# Arriquitaun2.net
KiCad netlist of a schematic drawn in Altium Designer
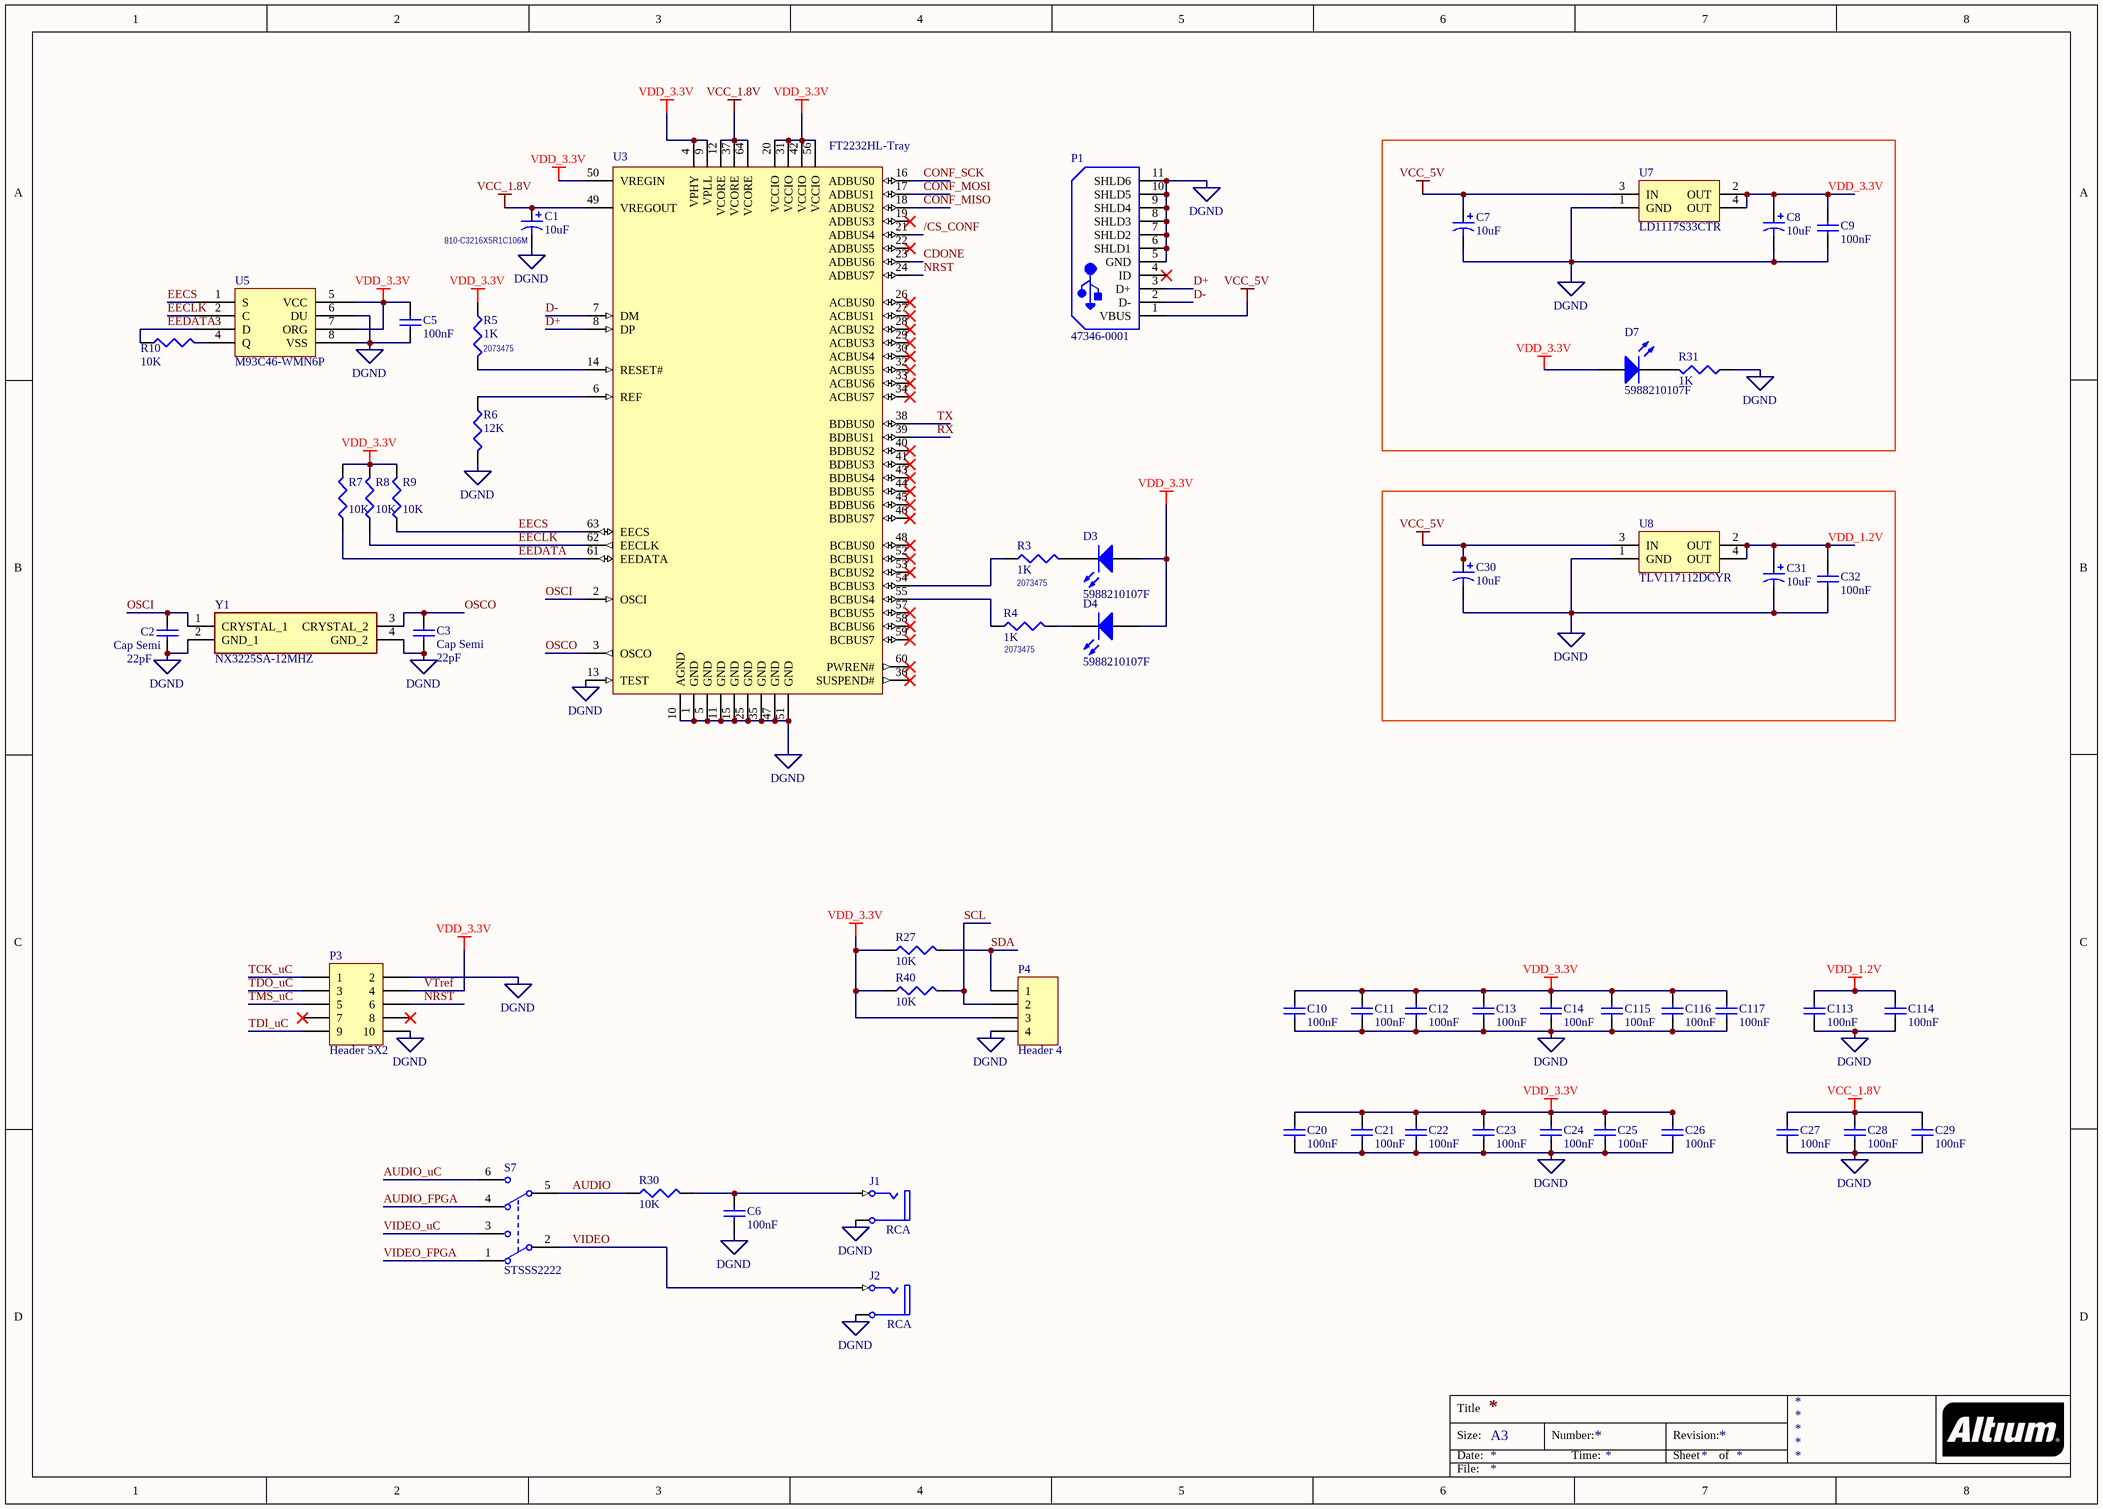
[diagram p0: Arriquitaun2.SchDoc]

(export (version "E")
  (design (tool "Eeschema 10.0.6"))
  (components
    (comp (ref "C1")
      (value "10uF")
      (footprint "C1206")
      (description "Polarized Capacitor (Radial)")
      (fields
        (field (name "SUPPLIER PART NUMBER 1") "810-C3216X5R1C106M")
        (field (name "Comment") "Cap Pol1")
        (field (name "PUBLISHER") "Altium Limited")
      )
      (libsource (lib "Miscellaneous Devices") (part "Cap Pol1"))
    )
    (comp (ref "C2")
      (value "Cap Semi")
      (footprint "C1206")
      (description "Capacitor (Semiconductor SIM Model)")
      (fields (field (name "ALTIUM_VALUE") "22pF") (field (name "PUBLISHER") "Altium Limited"))
      (libsource (lib "Miscellaneous Devices") (part "Cap Semi"))
    )
    (comp (ref "C3")
      (value "Cap Semi")
      (footprint "C1206")
      (description "Capacitor (Semiconductor SIM Model)")
      (fields (field (name "ALTIUM_VALUE") "22pF") (field (name "PUBLISHER") "Altium Limited"))
      (libsource (lib "Miscellaneous Devices") (part "Cap Semi"))
    )
    (comp (ref "C5")
      (value "100nF")
      (footprint "C1206")
      (description "Capacitor (Semiconductor SIM Model)")
      (fields (field (name "Comment") "Cap Semi") (field (name "PUBLISHER") "Altium Limited"))
      (libsource (lib "Miscellaneous Devices") (part "Cap Semi"))
    )
    (comp (ref "C6")
      (value "100nF")
      (footprint "C1206")
      (description "Capacitor (Semiconductor SIM Model)")
      (fields (field (name "Comment") "Cap Semi") (field (name "PUBLISHER") "Altium Limited"))
      (libsource (lib "Miscellaneous Devices") (part "Cap Semi"))
    )
    (comp (ref "C7")
      (value "10uF")
      (footprint "C1206")
      (description "Polarized Capacitor (Radial)")
      (fields (field (name "Comment") "Cap Pol1") (field (name "PUBLISHER") "Altium Limited"))
      (libsource (lib "Miscellaneous Devices") (part "Cap Pol1"))
    )
    (comp (ref "C8")
      (value "10uF")
      (footprint "C1206")
      (description "Polarized Capacitor (Radial)")
      (fields (field (name "Comment") "Cap Pol1") (field (name "PUBLISHER") "Altium Limited"))
      (libsource (lib "Miscellaneous Devices") (part "Cap Pol1"))
    )
    (comp (ref "C9")
      (value "100nF")
      (footprint "C1206")
      (description "Capacitor (Semiconductor SIM Model)")
      (fields (field (name "Comment") "Cap Semi") (field (name "PUBLISHER") "Altium Limited"))
      (libsource (lib "Miscellaneous Devices") (part "Cap Semi"))
    )
    (comp (ref "C10")
      (value "100nF")
      (footprint "C1206")
      (description "Capacitor (Semiconductor SIM Model)")
      (fields (field (name "Comment") "Cap Semi") (field (name "PUBLISHER") "Altium Limited"))
      (libsource (lib "Miscellaneous Devices") (part "Cap Semi"))
    )
    (comp (ref "C11")
      (value "100nF")
      (footprint "C1206")
      (description "Capacitor (Semiconductor SIM Model)")
      (fields (field (name "Comment") "Cap Semi") (field (name "PUBLISHER") "Altium Limited"))
      (libsource (lib "Miscellaneous Devices") (part "Cap Semi"))
    )
    (comp (ref "C12")
      (value "100nF")
      (footprint "C1206")
      (description "Capacitor (Semiconductor SIM Model)")
      (fields (field (name "Comment") "Cap Semi") (field (name "PUBLISHER") "Altium Limited"))
      (libsource (lib "Miscellaneous Devices") (part "Cap Semi"))
    )
    (comp (ref "C13")
      (value "100nF")
      (footprint "C1206")
      (description "Capacitor (Semiconductor SIM Model)")
      (fields (field (name "Comment") "Cap Semi") (field (name "PUBLISHER") "Altium Limited"))
      (libsource (lib "Miscellaneous Devices") (part "Cap Semi"))
    )
    (comp (ref "C14")
      (value "100nF")
      (footprint "C1206")
      (description "Capacitor (Semiconductor SIM Model)")
      (fields (field (name "Comment") "Cap Semi") (field (name "PUBLISHER") "Altium Limited"))
      (libsource (lib "Miscellaneous Devices") (part "Cap Semi"))
    )
    (comp (ref "C20")
      (value "100nF")
      (footprint "C1206")
      (description "Capacitor (Semiconductor SIM Model)")
      (fields (field (name "Comment") "Cap Semi") (field (name "PUBLISHER") "Altium Limited"))
      (libsource (lib "Miscellaneous Devices") (part "Cap Semi"))
    )
    (comp (ref "C21")
      (value "100nF")
      (footprint "C1206")
      (description "Capacitor (Semiconductor SIM Model)")
      (fields (field (name "Comment") "Cap Semi") (field (name "PUBLISHER") "Altium Limited"))
      (libsource (lib "Miscellaneous Devices") (part "Cap Semi"))
    )
    (comp (ref "C22")
      (value "100nF")
      (footprint "C1206")
      (description "Capacitor (Semiconductor SIM Model)")
      (fields (field (name "Comment") "Cap Semi") (field (name "PUBLISHER") "Altium Limited"))
      (libsource (lib "Miscellaneous Devices") (part "Cap Semi"))
    )
    (comp (ref "C23")
      (value "100nF")
      (footprint "C1206")
      (description "Capacitor (Semiconductor SIM Model)")
      (fields (field (name "Comment") "Cap Semi") (field (name "PUBLISHER") "Altium Limited"))
      (libsource (lib "Miscellaneous Devices") (part "Cap Semi"))
    )
    (comp (ref "C24")
      (value "100nF")
      (footprint "C1206")
      (description "Capacitor (Semiconductor SIM Model)")
      (fields (field (name "Comment") "Cap Semi") (field (name "PUBLISHER") "Altium Limited"))
      (libsource (lib "Miscellaneous Devices") (part "Cap Semi"))
    )
    (comp (ref "C25")
      (value "100nF")
      (footprint "C1206")
      (description "Capacitor (Semiconductor SIM Model)")
      (fields (field (name "Comment") "Cap Semi") (field (name "PUBLISHER") "Altium Limited"))
      (libsource (lib "Miscellaneous Devices") (part "Cap Semi"))
    )
    (comp (ref "C26")
      (value "100nF")
      (footprint "C1206")
      (description "Capacitor (Semiconductor SIM Model)")
      (fields (field (name "Comment") "Cap Semi") (field (name "PUBLISHER") "Altium Limited"))
      (libsource (lib "Miscellaneous Devices") (part "Cap Semi"))
    )
    (comp (ref "C27")
      (value "100nF")
      (footprint "C1206")
      (description "Capacitor (Semiconductor SIM Model)")
      (fields (field (name "Comment") "Cap Semi") (field (name "PUBLISHER") "Altium Limited"))
      (libsource (lib "Miscellaneous Devices") (part "Cap Semi"))
    )
    (comp (ref "C28")
      (value "100nF")
      (footprint "C1206")
      (description "Capacitor (Semiconductor SIM Model)")
      (fields (field (name "Comment") "Cap Semi") (field (name "PUBLISHER") "Altium Limited"))
      (libsource (lib "Miscellaneous Devices") (part "Cap Semi"))
    )
    (comp (ref "C29")
      (value "100nF")
      (footprint "C1206")
      (description "Capacitor (Semiconductor SIM Model)")
      (fields (field (name "Comment") "Cap Semi") (field (name "PUBLISHER") "Altium Limited"))
      (libsource (lib "Miscellaneous Devices") (part "Cap Semi"))
    )
    (comp (ref "C30")
      (value "10uF")
      (footprint "C1206")
      (description "Polarized Capacitor (Radial)")
      (fields (field (name "Comment") "Cap Pol1") (field (name "PUBLISHER") "Altium Limited"))
      (libsource (lib "Miscellaneous Devices") (part "Cap Pol1"))
    )
    (comp (ref "C31")
      (value "10uF")
      (footprint "C1206")
      (description "Polarized Capacitor (Radial)")
      (fields (field (name "Comment") "Cap Pol1") (field (name "PUBLISHER") "Altium Limited"))
      (libsource (lib "Miscellaneous Devices") (part "Cap Pol1"))
    )
    (comp (ref "C32")
      (value "100nF")
      (footprint "C1206")
      (description "Capacitor (Semiconductor SIM Model)")
      (fields (field (name "Comment") "Cap Semi") (field (name "PUBLISHER") "Altium Limited"))
      (libsource (lib "Miscellaneous Devices") (part "Cap Semi"))
    )
    (comp (ref "C113")
      (value "100nF")
      (footprint "C1206")
      (description "Capacitor (Semiconductor SIM Model)")
      (fields (field (name "Comment") "Cap Semi") (field (name "PUBLISHER") "Altium Limited"))
      (libsource (lib "Miscellaneous Devices") (part "Cap Semi"))
    )
    (comp (ref "C114")
      (value "100nF")
      (footprint "C1206")
      (description "Capacitor (Semiconductor SIM Model)")
      (fields (field (name "Comment") "Cap Semi") (field (name "PUBLISHER") "Altium Limited"))
      (libsource (lib "Miscellaneous Devices") (part "Cap Semi"))
    )
    (comp (ref "C115")
      (value "100nF")
      (footprint "C1206")
      (description "Capacitor (Semiconductor SIM Model)")
      (fields (field (name "Comment") "Cap Semi") (field (name "PUBLISHER") "Altium Limited"))
      (libsource (lib "Miscellaneous Devices") (part "Cap Semi"))
    )
    (comp (ref "C116")
      (value "100nF")
      (footprint "C1206")
      (description "Capacitor (Semiconductor SIM Model)")
      (fields (field (name "Comment") "Cap Semi") (field (name "PUBLISHER") "Altium Limited"))
      (libsource (lib "Miscellaneous Devices") (part "Cap Semi"))
    )
    (comp (ref "C117")
      (value "100nF")
      (footprint "C1206")
      (description "Capacitor (Semiconductor SIM Model)")
      (fields (field (name "Comment") "Cap Semi") (field (name "PUBLISHER") "Altium Limited"))
      (libsource (lib "Miscellaneous Devices") (part "Cap Semi"))
    )
    (comp (ref "D3")
      (value "5988210107F")
      (footprint "1206 - LED")
      (description "LED, Rojo, Montaje Superficial, 1206 (Métrico 3216), 20 mA, 2 V, 640 nm")
      (fields (field (name "PUBLISHER") "Altium Limited"))
      (libsource (lib "Arriquitaun") (part "5988210107F"))
    )
    (comp (ref "D4")
      (value "5988210107F")
      (footprint "1206 - LED")
      (description "LED, Rojo, Montaje Superficial, 1206 (Métrico 3216), 20 mA, 2 V, 640 nm")
      (fields (field (name "PUBLISHER") "Altium Limited"))
      (libsource (lib "Arriquitaun") (part "5988210107F"))
    )
    (comp (ref "D7")
      (value "5988210107F")
      (footprint "1206 - LED")
      (description "LED, Rojo, Montaje Superficial, 1206 (Métrico 3216), 20 mA, 2 V, 640 nm")
      (fields (field (name "PUBLISHER") "Altium Limited"))
      (libsource (lib "Arriquitaun") (part "5988210107F"))
    )
    (comp (ref "J1")
      (value "RCA")
      (footprint "161")
      (description "RCA Phono Jack, Right Angle, Thru-Hole, Snap-In")
      (fields (field (name "PUBLISHER") "Altium Limited"))
      (libsource (lib "Miscellaneous Connectors") (part "RCA"))
    )
    (comp (ref "J2")
      (value "RCA")
      (footprint "161")
      (description "RCA Phono Jack, Right Angle, Thru-Hole, Snap-In")
      (fields (field (name "PUBLISHER") "Altium Limited"))
      (libsource (lib "Miscellaneous Connectors") (part "RCA"))
    )
    (comp (ref "P1")
      (value "47346-0001")
      (footprint "USB-MICRO-B_V")
      (description "Conectores USB MICRO USB B RECPT BTTM MOUNT ASSY")
      (libsource (lib "Arriquitaun") (part "47346-0001"))
    )
    (comp (ref "P3")
      (value "Header 5X2")
      (footprint "HDR2X5")
      (description "Header, 5-Pin, Dual row")
      (fields (field (name "PUBLISHER") "Altium Limited"))
      (libsource (lib "Miscellaneous Connectors") (part "Header 5X2"))
    )
    (comp (ref "P4")
      (value "Header 4")
      (footprint "HDR1X4")
      (description "Header, 4-Pin")
      (fields (field (name "PUBLISHER") "Altium Limited"))
      (libsource (lib "Miscellaneous Connectors") (part "Header 4"))
    )
    (comp (ref "R3")
      (value "1K")
      (footprint "c1206")
      (description "Resistor")
      (fields
        (field (name "SUPPLIER PART NUMBER 1") "2073475")
        (field (name "Comment") "Res3")
        (field (name "PUBLISHER") "Altium Limited")
      )
      (libsource (lib "Miscellaneous Devices") (part "Res3"))
    )
    (comp (ref "R4")
      (value "1K")
      (footprint "c1206")
      (description "Resistor")
      (fields
        (field (name "SUPPLIER PART NUMBER 1") "2073475")
        (field (name "Comment") "Res3")
        (field (name "PUBLISHER") "Altium Limited")
      )
      (libsource (lib "Miscellaneous Devices") (part "Res3"))
    )
    (comp (ref "R5")
      (value "1K")
      (footprint "c1206")
      (description "Resistor")
      (fields
        (field (name "SUPPLIER PART NUMBER 1") "2073475")
        (field (name "Comment") "Res3")
        (field (name "PUBLISHER") "Altium Limited")
      )
      (libsource (lib "Miscellaneous Devices") (part "Res3"))
    )
    (comp (ref "R6")
      (value "12K")
      (footprint "c1206")
      (description "Resistor")
      (fields (field (name "Comment") "Res3") (field (name "PUBLISHER") "Altium Limited"))
      (libsource (lib "Miscellaneous Devices") (part "Res3"))
    )
    (comp (ref "R7")
      (value "10K")
      (footprint "c1206")
      (description "Resistor")
      (fields (field (name "Comment") "Res3") (field (name "PUBLISHER") "Altium Limited"))
      (libsource (lib "Miscellaneous Devices") (part "Res3"))
    )
    (comp (ref "R8")
      (value "10K")
      (footprint "c1206")
      (description "Resistor")
      (fields (field (name "Comment") "Res3") (field (name "PUBLISHER") "Altium Limited"))
      (libsource (lib "Miscellaneous Devices") (part "Res3"))
    )
    (comp (ref "R9")
      (value "10K")
      (footprint "c1206")
      (description "Resistor")
      (fields (field (name "Comment") "Res3") (field (name "PUBLISHER") "Altium Limited"))
      (libsource (lib "Miscellaneous Devices") (part "Res3"))
    )
    (comp (ref "R10")
      (value "10K")
      (footprint "c1206")
      (description "Resistor")
      (fields (field (name "Comment") "Res3") (field (name "PUBLISHER") "Altium Limited"))
      (libsource (lib "Miscellaneous Devices") (part "Res3"))
    )
    (comp (ref "R27")
      (value "10K")
      (footprint "c1206")
      (description "Resistor")
      (fields (field (name "Comment") "Res3") (field (name "PUBLISHER") "Altium Limited"))
      (libsource (lib "Miscellaneous Devices") (part "Res3"))
    )
    (comp (ref "R30")
      (value "10K")
      (footprint "c1206")
      (description "Resistor")
      (fields (field (name "Comment") "Res3") (field (name "PUBLISHER") "Altium Limited"))
      (libsource (lib "Miscellaneous Devices") (part "Res3"))
    )
    (comp (ref "R31")
      (value "1K")
      (footprint "c1206")
      (description "Resistor")
      (fields (field (name "Comment") "Res3") (field (name "PUBLISHER") "Altium Limited"))
      (libsource (lib "Miscellaneous Devices") (part "Res3"))
    )
    (comp (ref "R40")
      (value "10K")
      (footprint "c1206")
      (description "Resistor")
      (fields (field (name "Comment") "Res3") (field (name "PUBLISHER") "Altium Limited"))
      (libsource (lib "Miscellaneous Devices") (part "Res3"))
    )
    (comp (ref "S7")
      (value "STSSS2222")
      (footprint "SWITCH")
      (description "Interruptor Deslizante, DPDT, Taladro Pasante, Serie STSS2, 300 mA")
      (libsource (lib "Arriquitaun") (part "STSSS2222"))
    )
    (comp (ref "U3")
      (value "FT2232HL-Tray")
      (footprint "LQFP-64_N")
      (description "Dual High Speed USB To Multipurpose UART/FIFO IC, 64-pin LQFP, Tray")
      (fields (field (name "MANUFACTURER") "FTDI"))
      (libsource (lib "Arriquitaun") (part "FT2232HL-Tray"))
    )
    (comp (ref "U5")
      (value "M93C46-WMN6P")
      (footprint "SOP8_N")
      (description "EEPROM 1 Kbit (128 x 8) 2.5V to 5.5V EEProm")
      (libsource (lib "Arriquitaun") (part "M93C46-WMN6P"))
    )
    (comp (ref "U7")
      (value "LD1117S33CTR")
      (footprint "ZZ311")
      (description "800mA and 1A Low Dropout Positive Regulator 2.85V, 3.3V, 5V, and Adjustable")
      (fields (field (name "PUBLISHER") "Altium Limited"))
      (libsource (lib "Arriquitaun") (part "LD1117S33CTR"))
    )
    (comp (ref "U8")
      (value "TLV117112DCYR")
      (footprint "ZZ311")
      (description "Reguladores de voltaje LDO 1A + Fixed Vltg Lo-Drpout Linear Reg")
      (fields (field (name "PUBLISHER") "Altium Limited"))
      (libsource (lib "Arriquitaun") (part "TLV117112DCYR"))
    )
    (comp (ref "Y1")
      (value "NX3225SA-12MHZ")
      (footprint "NX3225SA12000MHZSTDCSR1")
      (description "Crystal or Oscillator")
      (fields
        (field (name "MANUFACTURER_PART_NUMBER") "NX3225SA-24.000M-STD-CSR-3")
        (field (name "MOUSER PART NUMBER") "344-NX3225SA24MSTSR3")
      )
      (libsource (lib "Arriquitaun") (part "NX3225SA-12MHZ-STD-CSR-3"))
    )
  )
  (nets
    (net (code "1") (name "/AUDIO") (class "Default")
      (node (ref "R30") (pin "1") (pinfunction "1_1") (pintype "passive"))
      (node (ref "S7") (pin "5") (pinfunction "COMMON2_5") (pintype "passive"))
    )
    (net (code "2") (name "/AUDIO_FPGA") (class "Default")
      (node (ref "S7") (pin "4") (pinfunction "NC2_4") (pintype "passive"))
    )
    (net (code "3") (name "/AUDIO_uC") (class "Default")
      (node (ref "S7") (pin "6") (pinfunction "NO2_6") (pintype "passive"))
    )
    (net (code "4") (name "/CDONE") (class "Default")
      (node (ref "U3") (pin "23") (pinfunction "ADBUS6_23") (pintype "bidirectional"))
    )
    (net (code "5") (name "/CONF_MISO") (class "Default")
      (node (ref "U3") (pin "18") (pinfunction "ADBUS2_18") (pintype "bidirectional"))
    )
    (net (code "6") (name "/CONF_MOSI") (class "Default")
      (node (ref "U3") (pin "17") (pinfunction "ADBUS1_17") (pintype "bidirectional"))
    )
    (net (code "7") (name "/CONF_SCK") (class "Default")
      (node (ref "U3") (pin "16") (pinfunction "ADBUS0_16") (pintype "bidirectional"))
    )
    (net (code "8") (name "/D+") (class "Default")
      (node (ref "P1") (pin "3") (pinfunction "D+_3") (pintype "passive"))
      (node (ref "U3") (pin "8") (pinfunction "DP_8") (pintype "input"))
    )
    (net (code "9") (name "/D-") (class "Default")
      (node (ref "P1") (pin "2") (pinfunction "D-_2") (pintype "passive"))
      (node (ref "U3") (pin "7") (pinfunction "DM_7") (pintype "input"))
    )
    (net (code "10") (name "/EECLK") (class "Default")
      (node (ref "R8") (pin "1") (pinfunction "1_1") (pintype "passive"))
      (node (ref "U3") (pin "62") (pinfunction "EECLK_62") (pintype "output"))
      (node (ref "U5") (pin "2") (pinfunction "C_2") (pintype "passive"))
    )
    (net (code "11") (name "/EECS") (class "Default")
      (node (ref "R9") (pin "1") (pinfunction "1_1") (pintype "passive"))
      (node (ref "U3") (pin "63") (pinfunction "EECS_63") (pintype "bidirectional"))
      (node (ref "U5") (pin "1") (pinfunction "S_1") (pintype "passive"))
    )
    (net (code "12") (name "/EEDATA") (class "Default")
      (node (ref "R10") (pin "1") (pinfunction "1_1") (pintype "passive"))
      (node (ref "R7") (pin "1") (pinfunction "1_1") (pintype "passive"))
      (node (ref "U3") (pin "61") (pinfunction "EEDATA_61") (pintype "bidirectional"))
      (node (ref "U5") (pin "3") (pinfunction "D_3") (pintype "passive"))
    )
    (net (code "13") (name "/NRST") (class "Default")
      (node (ref "P3") (pin "6") (pinfunction "6_6") (pintype "passive"))
      (node (ref "U3") (pin "24") (pinfunction "ADBUS7_24") (pintype "bidirectional"))
    )
    (net (code "14") (name "/OSCI") (class "Default")
      (node (ref "C2") (pin "1") (pinfunction "1_1") (pintype "passive"))
      (node (ref "U3") (pin "2") (pinfunction "OSCI_2") (pintype "input"))
      (node (ref "Y1") (pin "1") (pinfunction "CRYSTAL_1_1") (pintype "passive"))
    )
    (net (code "15") (name "/OSCO") (class "Default")
      (node (ref "C3") (pin "2") (pinfunction "2_2") (pintype "passive"))
      (node (ref "U3") (pin "3") (pinfunction "OSCO_3") (pintype "output"))
      (node (ref "Y1") (pin "3") (pinfunction "CRYSTAL_2_3") (pintype "passive"))
    )
    (net (code "16") (name "/RX") (class "Default")
      (node (ref "U3") (pin "39") (pinfunction "BDBUS1_39") (pintype "bidirectional"))
    )
    (net (code "17") (name "/SCL") (class "Default")
      (node (ref "P4") (pin "2") (pinfunction "2_2") (pintype "passive"))
      (node (ref "R40") (pin "2") (pinfunction "2_2") (pintype "passive"))
    )
    (net (code "18") (name "/SDA") (class "Default")
      (node (ref "P4") (pin "1") (pinfunction "1_1") (pintype "passive"))
      (node (ref "R27") (pin "2") (pinfunction "2_2") (pintype "passive"))
    )
    (net (code "19") (name "/TCK_uC") (class "Default")
      (node (ref "P3") (pin "1") (pinfunction "1_1") (pintype "passive"))
    )
    (net (code "20") (name "/TDI_uC") (class "Default")
      (node (ref "P3") (pin "9") (pinfunction "9_9") (pintype "passive"))
    )
    (net (code "21") (name "/TDO_uC") (class "Default")
      (node (ref "P3") (pin "3") (pinfunction "3_3") (pintype "passive"))
    )
    (net (code "22") (name "/TMS_uC") (class "Default")
      (node (ref "P3") (pin "5") (pinfunction "5_5") (pintype "passive"))
    )
    (net (code "23") (name "/TX") (class "Default")
      (node (ref "U3") (pin "38") (pinfunction "BDBUS0_38") (pintype "bidirectional"))
    )
    (net (code "24") (name "/VIDEO") (class "Default")
      (node (ref "J2") (pin "2B") (pinfunction "Signal_2B") (pintype "input"))
      (node (ref "S7") (pin "2") (pinfunction "COMMON1_2") (pintype "passive"))
    )
    (net (code "25") (name "/VIDEO_FPGA") (class "Default")
      (node (ref "S7") (pin "1") (pinfunction "NC1_1") (pintype "passive"))
    )
    (net (code "26") (name "/VIDEO_uC") (class "Default")
      (node (ref "S7") (pin "3") (pinfunction "NO1_3") (pintype "passive"))
    )
    (net (code "27") (name "/{slash}CS_CONF") (class "Default")
      (node (ref "U3") (pin "21") (pinfunction "ADBUS4_21") (pintype "bidirectional"))
    )
    (net (code "28") (name "DGND") (class "Default")
      (node (ref "C1") (pin "2") (pinfunction "2_2") (pintype "passive"))
      (node (ref "C10") (pin "1") (pinfunction "1_1") (pintype "passive"))
      (node (ref "C11") (pin "1") (pinfunction "1_1") (pintype "passive"))
      (node (ref "C113") (pin "1") (pinfunction "1_1") (pintype "passive"))
      (node (ref "C114") (pin "1") (pinfunction "1_1") (pintype "passive"))
      (node (ref "C115") (pin "1") (pinfunction "1_1") (pintype "passive"))
      (node (ref "C116") (pin "1") (pinfunction "1_1") (pintype "passive"))
      (node (ref "C117") (pin "1") (pinfunction "1_1") (pintype "passive"))
      (node (ref "C12") (pin "1") (pinfunction "1_1") (pintype "passive"))
      (node (ref "C13") (pin "1") (pinfunction "1_1") (pintype "passive"))
      (node (ref "C14") (pin "1") (pinfunction "1_1") (pintype "passive"))
      (node (ref "C2") (pin "2") (pinfunction "2_2") (pintype "passive"))
      (node (ref "C20") (pin "1") (pinfunction "1_1") (pintype "passive"))
      (node (ref "C21") (pin "1") (pinfunction "1_1") (pintype "passive"))
      (node (ref "C22") (pin "1") (pinfunction "1_1") (pintype "passive"))
      (node (ref "C23") (pin "1") (pinfunction "1_1") (pintype "passive"))
      (node (ref "C24") (pin "1") (pinfunction "1_1") (pintype "passive"))
      (node (ref "C25") (pin "1") (pinfunction "1_1") (pintype "passive"))
      (node (ref "C26") (pin "1") (pinfunction "1_1") (pintype "passive"))
      (node (ref "C27") (pin "1") (pinfunction "1_1") (pintype "passive"))
      (node (ref "C28") (pin "1") (pinfunction "1_1") (pintype "passive"))
      (node (ref "C29") (pin "1") (pinfunction "1_1") (pintype "passive"))
      (node (ref "C3") (pin "1") (pinfunction "1_1") (pintype "passive"))
      (node (ref "C30") (pin "2") (pinfunction "2_2") (pintype "passive"))
      (node (ref "C31") (pin "2") (pinfunction "2_2") (pintype "passive"))
      (node (ref "C32") (pin "1") (pinfunction "1_1") (pintype "passive"))
      (node (ref "C5") (pin "1") (pinfunction "1_1") (pintype "passive"))
      (node (ref "C6") (pin "1") (pinfunction "1_1") (pintype "passive"))
      (node (ref "C7") (pin "2") (pinfunction "2_2") (pintype "passive"))
      (node (ref "C8") (pin "2") (pinfunction "2_2") (pintype "passive"))
      (node (ref "C9") (pin "1") (pinfunction "1_1") (pintype "passive"))
      (node (ref "J1") (pin "1A") (pinfunction "Ground_1A") (pintype "power_in"))
      (node (ref "J2") (pin "1A") (pinfunction "Ground_1A") (pintype "power_in"))
      (node (ref "P1") (pin "10") (pinfunction "SHLD5_10") (pintype "passive"))
      (node (ref "P1") (pin "11") (pinfunction "SHLD6_11") (pintype "passive"))
      (node (ref "P1") (pin "5") (pinfunction "GND_5") (pintype "passive"))
      (node (ref "P1") (pin "6") (pinfunction "SHLD1_6") (pintype "passive"))
      (node (ref "P1") (pin "7") (pinfunction "SHLD2_7") (pintype "passive"))
      (node (ref "P1") (pin "8") (pinfunction "SHLD3_8") (pintype "passive"))
      (node (ref "P1") (pin "9") (pinfunction "SHLD4_9") (pintype "passive"))
      (node (ref "P3") (pin "10") (pinfunction "10_10") (pintype "passive"))
      (node (ref "P3") (pin "2") (pinfunction "2_2") (pintype "passive"))
      (node (ref "P4") (pin "4") (pinfunction "4_4") (pintype "passive"))
      (node (ref "R31") (pin "1") (pinfunction "1_1") (pintype "passive"))
      (node (ref "R6") (pin "2") (pinfunction "2_2") (pintype "passive"))
      (node (ref "U3") (pin "1") (pinfunction "GND_1") (pintype "power_in"))
      (node (ref "U3") (pin "10") (pinfunction "AGND_10") (pintype "power_in"))
      (node (ref "U3") (pin "11") (pinfunction "GND_11") (pintype "power_in"))
      (node (ref "U3") (pin "13") (pinfunction "TEST_13") (pintype "input"))
      (node (ref "U3") (pin "15") (pinfunction "GND_15") (pintype "power_in"))
      (node (ref "U3") (pin "25") (pinfunction "GND_25") (pintype "power_in"))
      (node (ref "U3") (pin "35") (pinfunction "GND_35") (pintype "power_in"))
      (node (ref "U3") (pin "47") (pinfunction "GND_47") (pintype "power_in"))
      (node (ref "U3") (pin "5") (pinfunction "GND_5") (pintype "power_in"))
      (node (ref "U3") (pin "51") (pinfunction "GND_51") (pintype "power_in"))
      (node (ref "U5") (pin "6") (pinfunction "DU_6") (pintype "passive"))
      (node (ref "U5") (pin "8") (pinfunction "VSS_8") (pintype "power_in"))
      (node (ref "U7") (pin "1") (pinfunction "GND_1") (pintype "power_in"))
      (node (ref "U8") (pin "1") (pinfunction "GND_1") (pintype "power_in"))
      (node (ref "Y1") (pin "2") (pinfunction "GND_1_2") (pintype "passive"))
      (node (ref "Y1") (pin "4") (pinfunction "GND_2_4") (pintype "passive"))
    )
    (net (code "29") (name "Net-(D3-K)") (class "Default")
      (node (ref "D3") (pin "2") (pinfunction "K_2") (pintype "passive"))
      (node (ref "R3") (pin "2") (pinfunction "2_2") (pintype "passive"))
    )
    (net (code "30") (name "Net-(D4-K)") (class "Default")
      (node (ref "D4") (pin "2") (pinfunction "K_2") (pintype "passive"))
      (node (ref "R4") (pin "2") (pinfunction "2_2") (pintype "passive"))
    )
    (net (code "31") (name "Net-(D7-K)") (class "Default")
      (node (ref "D7") (pin "2") (pinfunction "K_2") (pintype "passive"))
      (node (ref "R31") (pin "2") (pinfunction "2_2") (pintype "passive"))
    )
    (net (code "32") (name "Net-(J1-Signal)") (class "Default")
      (node (ref "C6") (pin "2") (pinfunction "2_2") (pintype "passive"))
      (node (ref "J1") (pin "2B") (pinfunction "Signal_2B") (pintype "input"))
      (node (ref "R30") (pin "2") (pinfunction "2_2") (pintype "passive"))
    )
    (net (code "33") (name "Net-(U3-BCBUS3)") (class "Default")
      (node (ref "R3") (pin "1") (pinfunction "1_1") (pintype "passive"))
      (node (ref "U3") (pin "54") (pinfunction "BCBUS3_54") (pintype "bidirectional"))
    )
    (net (code "34") (name "Net-(U3-BCBUS4)") (class "Default")
      (node (ref "R4") (pin "1") (pinfunction "1_1") (pintype "passive"))
      (node (ref "U3") (pin "55") (pinfunction "BCBUS4_55") (pintype "bidirectional"))
    )
    (net (code "35") (name "Net-(U3-REF)") (class "Default")
      (node (ref "R6") (pin "1") (pinfunction "1_1") (pintype "passive"))
      (node (ref "U3") (pin "6") (pinfunction "REF_6") (pintype "input"))
    )
    (net (code "36") (name "Net-(U3-RESET#)") (class "Default")
      (node (ref "R5") (pin "2") (pinfunction "2_2") (pintype "passive"))
      (node (ref "U3") (pin "14") (pinfunction "RESET#_14") (pintype "input"))
    )
    (net (code "37") (name "Net-(U5-Q)") (class "Default")
      (node (ref "R10") (pin "2") (pinfunction "2_2") (pintype "passive"))
      (node (ref "U5") (pin "4") (pinfunction "Q_4") (pintype "passive"))
    )
    (net (code "38") (name "VCC_1.8V") (class "Default")
      (node (ref "C1") (pin "1") (pinfunction "1_1") (pintype "passive"))
      (node (ref "C27") (pin "2") (pinfunction "2_2") (pintype "passive"))
      (node (ref "C28") (pin "2") (pinfunction "2_2") (pintype "passive"))
      (node (ref "C29") (pin "2") (pinfunction "2_2") (pintype "passive"))
      (node (ref "U3") (pin "12") (pinfunction "VCORE_12") (pintype "power_in"))
      (node (ref "U3") (pin "37") (pinfunction "VCORE_37") (pintype "power_in"))
      (node (ref "U3") (pin "49") (pinfunction "VREGOUT_49") (pintype "power_in"))
      (node (ref "U3") (pin "64") (pinfunction "VCORE_64") (pintype "power_in"))
    )
    (net (code "39") (name "VCC_5V") (class "Default")
      (node (ref "C30") (pin "1") (pinfunction "1_1") (pintype "passive"))
      (node (ref "C7") (pin "1") (pinfunction "1_1") (pintype "passive"))
      (node (ref "P1") (pin "1") (pinfunction "VBUS_1") (pintype "passive"))
      (node (ref "U7") (pin "3") (pinfunction "IN_3") (pintype "power_in"))
      (node (ref "U8") (pin "3") (pinfunction "IN_3") (pintype "power_in"))
    )
    (net (code "40") (name "VDD_1.2V") (class "Default")
      (node (ref "C113") (pin "2") (pinfunction "2_2") (pintype "passive"))
      (node (ref "C114") (pin "2") (pinfunction "2_2") (pintype "passive"))
      (node (ref "C31") (pin "1") (pinfunction "1_1") (pintype "passive"))
      (node (ref "C32") (pin "2") (pinfunction "2_2") (pintype "passive"))
      (node (ref "U8") (pin "2") (pinfunction "OUT_2") (pintype "power_in"))
      (node (ref "U8") (pin "4") (pinfunction "OUT_4") (pintype "power_in"))
    )
    (net (code "41") (name "VDD_3.3V") (class "Default")
      (node (ref "C10") (pin "2") (pinfunction "2_2") (pintype "passive"))
      (node (ref "C11") (pin "2") (pinfunction "2_2") (pintype "passive"))
      (node (ref "C115") (pin "2") (pinfunction "2_2") (pintype "passive"))
      (node (ref "C116") (pin "2") (pinfunction "2_2") (pintype "passive"))
      (node (ref "C117") (pin "2") (pinfunction "2_2") (pintype "passive"))
      (node (ref "C12") (pin "2") (pinfunction "2_2") (pintype "passive"))
      (node (ref "C13") (pin "2") (pinfunction "2_2") (pintype "passive"))
      (node (ref "C14") (pin "2") (pinfunction "2_2") (pintype "passive"))
      (node (ref "C20") (pin "2") (pinfunction "2_2") (pintype "passive"))
      (node (ref "C21") (pin "2") (pinfunction "2_2") (pintype "passive"))
      (node (ref "C22") (pin "2") (pinfunction "2_2") (pintype "passive"))
      (node (ref "C23") (pin "2") (pinfunction "2_2") (pintype "passive"))
      (node (ref "C24") (pin "2") (pinfunction "2_2") (pintype "passive"))
      (node (ref "C25") (pin "2") (pinfunction "2_2") (pintype "passive"))
      (node (ref "C26") (pin "2") (pinfunction "2_2") (pintype "passive"))
      (node (ref "C5") (pin "2") (pinfunction "2_2") (pintype "passive"))
      (node (ref "C8") (pin "1") (pinfunction "1_1") (pintype "passive"))
      (node (ref "C9") (pin "2") (pinfunction "2_2") (pintype "passive"))
      (node (ref "D3") (pin "1") (pinfunction "A_1") (pintype "passive"))
      (node (ref "D4") (pin "1") (pinfunction "A_1") (pintype "passive"))
      (node (ref "D7") (pin "1") (pinfunction "A_1") (pintype "passive"))
      (node (ref "P3") (pin "4") (pinfunction "4_4") (pintype "passive"))
      (node (ref "P4") (pin "3") (pinfunction "3_3") (pintype "passive"))
      (node (ref "R27") (pin "1") (pinfunction "1_1") (pintype "passive"))
      (node (ref "R40") (pin "1") (pinfunction "1_1") (pintype "passive"))
      (node (ref "R5") (pin "1") (pinfunction "1_1") (pintype "passive"))
      (node (ref "R7") (pin "2") (pinfunction "2_2") (pintype "passive"))
      (node (ref "R8") (pin "2") (pinfunction "2_2") (pintype "passive"))
      (node (ref "R9") (pin "2") (pinfunction "2_2") (pintype "passive"))
      (node (ref "U3") (pin "20") (pinfunction "VCCIO_20") (pintype "power_in"))
      (node (ref "U3") (pin "31") (pinfunction "VCCIO_31") (pintype "power_in"))
      (node (ref "U3") (pin "4") (pinfunction "VPHY_4") (pintype "power_in"))
      (node (ref "U3") (pin "42") (pinfunction "VCCIO_42") (pintype "power_in"))
      (node (ref "U3") (pin "50") (pinfunction "VREGIN_50") (pintype "power_in"))
      (node (ref "U3") (pin "56") (pinfunction "VCCIO_56") (pintype "power_in"))
      (node (ref "U3") (pin "9") (pinfunction "VPLL_9") (pintype "power_in"))
      (node (ref "U5") (pin "5") (pinfunction "VCC_5") (pintype "power_in"))
      (node (ref "U5") (pin "7") (pinfunction "ORG_7") (pintype "passive"))
      (node (ref "U7") (pin "2") (pinfunction "OUT_2") (pintype "power_in"))
      (node (ref "U7") (pin "4") (pinfunction "OUT_4") (pintype "power_in"))
    )
    (net (code "42") (name "unconnected-(P1-ID-Pad4)") (class "Default")
      (node (ref "P1") (pin "4") (pinfunction "ID_4") (pintype "passive+no_connect"))
    )
    (net (code "43") (name "unconnected-(P3-Pad7)") (class "Default")
      (node (ref "P3") (pin "7") (pinfunction "7_7") (pintype "passive+no_connect"))
    )
    (net (code "44") (name "unconnected-(P3-Pad8)") (class "Default")
      (node (ref "P3") (pin "8") (pinfunction "8_8") (pintype "passive+no_connect"))
    )
    (net (code "45") (name "unconnected-(U3-ACBUS0-Pad26)") (class "Default")
      (node (ref "U3") (pin "26") (pinfunction "ACBUS0_26") (pintype "bidirectional+no_connect"))
    )
    (net (code "46") (name "unconnected-(U3-ACBUS1-Pad27)") (class "Default")
      (node (ref "U3") (pin "27") (pinfunction "ACBUS1_27") (pintype "bidirectional+no_connect"))
    )
    (net (code "47") (name "unconnected-(U3-ACBUS2-Pad28)") (class "Default")
      (node (ref "U3") (pin "28") (pinfunction "ACBUS2_28") (pintype "bidirectional+no_connect"))
    )
    (net (code "48") (name "unconnected-(U3-ACBUS3-Pad29)") (class "Default")
      (node (ref "U3") (pin "29") (pinfunction "ACBUS3_29") (pintype "bidirectional+no_connect"))
    )
    (net (code "49") (name "unconnected-(U3-ACBUS4-Pad30)") (class "Default")
      (node (ref "U3") (pin "30") (pinfunction "ACBUS4_30") (pintype "bidirectional+no_connect"))
    )
    (net (code "50") (name "unconnected-(U3-ACBUS5-Pad32)") (class "Default")
      (node (ref "U3") (pin "32") (pinfunction "ACBUS5_32") (pintype "bidirectional+no_connect"))
    )
    (net (code "51") (name "unconnected-(U3-ACBUS6-Pad33)") (class "Default")
      (node (ref "U3") (pin "33") (pinfunction "ACBUS6_33") (pintype "bidirectional+no_connect"))
    )
    (net (code "52") (name "unconnected-(U3-ACBUS7-Pad34)") (class "Default")
      (node (ref "U3") (pin "34") (pinfunction "ACBUS7_34") (pintype "bidirectional+no_connect"))
    )
    (net (code "53") (name "unconnected-(U3-ADBUS3-Pad19)") (class "Default")
      (node (ref "U3") (pin "19") (pinfunction "ADBUS3_19") (pintype "bidirectional+no_connect"))
    )
    (net (code "54") (name "unconnected-(U3-ADBUS5-Pad22)") (class "Default")
      (node (ref "U3") (pin "22") (pinfunction "ADBUS5_22") (pintype "bidirectional+no_connect"))
    )
    (net (code "55") (name "unconnected-(U3-BCBUS0-Pad48)") (class "Default")
      (node (ref "U3") (pin "48") (pinfunction "BCBUS0_48") (pintype "bidirectional+no_connect"))
    )
    (net (code "56") (name "unconnected-(U3-BCBUS1-Pad52)") (class "Default")
      (node (ref "U3") (pin "52") (pinfunction "BCBUS1_52") (pintype "bidirectional+no_connect"))
    )
    (net (code "57") (name "unconnected-(U3-BCBUS2-Pad53)") (class "Default")
      (node (ref "U3") (pin "53") (pinfunction "BCBUS2_53") (pintype "bidirectional+no_connect"))
    )
    (net (code "58") (name "unconnected-(U3-BCBUS5-Pad57)") (class "Default")
      (node (ref "U3") (pin "57") (pinfunction "BCBUS5_57") (pintype "bidirectional+no_connect"))
    )
    (net (code "59") (name "unconnected-(U3-BCBUS6-Pad58)") (class "Default")
      (node (ref "U3") (pin "58") (pinfunction "BCBUS6_58") (pintype "bidirectional+no_connect"))
    )
    (net (code "60") (name "unconnected-(U3-BCBUS7-Pad59)") (class "Default")
      (node (ref "U3") (pin "59") (pinfunction "BCBUS7_59") (pintype "bidirectional+no_connect"))
    )
    (net (code "61") (name "unconnected-(U3-BDBUS2-Pad40)") (class "Default")
      (node (ref "U3") (pin "40") (pinfunction "BDBUS2_40") (pintype "bidirectional+no_connect"))
    )
    (net (code "62") (name "unconnected-(U3-BDBUS3-Pad41)") (class "Default")
      (node (ref "U3") (pin "41") (pinfunction "BDBUS3_41") (pintype "bidirectional+no_connect"))
    )
    (net (code "63") (name "unconnected-(U3-BDBUS4-Pad43)") (class "Default")
      (node (ref "U3") (pin "43") (pinfunction "BDBUS4_43") (pintype "bidirectional+no_connect"))
    )
    (net (code "64") (name "unconnected-(U3-BDBUS5-Pad44)") (class "Default")
      (node (ref "U3") (pin "44") (pinfunction "BDBUS5_44") (pintype "bidirectional+no_connect"))
    )
    (net (code "65") (name "unconnected-(U3-BDBUS6-Pad45)") (class "Default")
      (node (ref "U3") (pin "45") (pinfunction "BDBUS6_45") (pintype "bidirectional+no_connect"))
    )
    (net (code "66") (name "unconnected-(U3-BDBUS7-Pad46)") (class "Default")
      (node (ref "U3") (pin "46") (pinfunction "BDBUS7_46") (pintype "bidirectional+no_connect"))
    )
    (net (code "67") (name "unconnected-(U3-PWREN#-Pad60)") (class "Default")
      (node (ref "U3") (pin "60") (pinfunction "PWREN#_60") (pintype "output+no_connect"))
    )
    (net (code "68") (name "unconnected-(U3-SUSPEND#-Pad36)") (class "Default")
      (node (ref "U3") (pin "36") (pinfunction "SUSPEND#_36") (pintype "output+no_connect"))
    )
  )
)
